# PCIe.net
KiCad netlist of a schematic drawn in Altium Designer
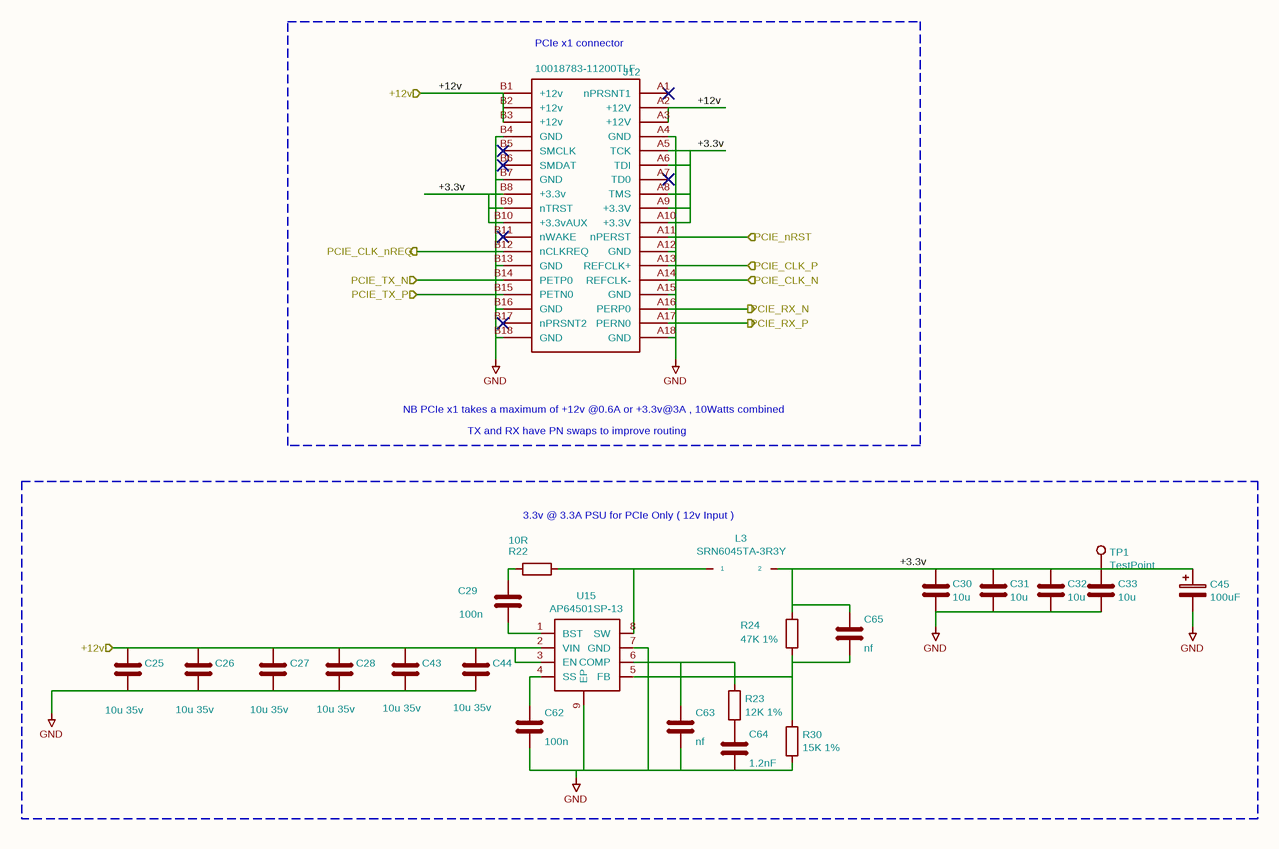
[diagram p0: PCIe.SchDoc]

(export (version "E")
  (design (tool "Eeschema 10.0.6"))
  (components
    (comp (ref "C25") (value "10u 35v") (libsource (lib "Device") (part "C")))
    (comp (ref "C26") (value "10u 35v") (libsource (lib "Device") (part "C")))
    (comp (ref "C27") (value "10u 35v") (libsource (lib "Device") (part "C")))
    (comp (ref "C28") (value "10u 35v") (libsource (lib "Device") (part "C")))
    (comp (ref "C29") (value "100n") (libsource (lib "Device") (part "C")))
    (comp (ref "C30") (value "10u") (libsource (lib "Device") (part "C")))
    (comp (ref "C31") (value "10u") (libsource (lib "Device") (part "C")))
    (comp (ref "C32") (value "10u") (libsource (lib "Device") (part "C")))
    (comp (ref "C33") (value "10u") (libsource (lib "Device") (part "C")))
    (comp (ref "C43") (value "10u 35v") (libsource (lib "Device") (part "C")))
    (comp (ref "C44") (value "10u 35v") (libsource (lib "Device") (part "C")))
    (comp (ref "C45") (value "100uF") (libsource (lib "Device") (part "CP")))
    (comp (ref "C62") (value "100n") (libsource (lib "Device") (part "C")))
    (comp (ref "C63") (value "nf") (libsource (lib "Device") (part "C")))
    (comp (ref "C64") (value "1.2nF") (libsource (lib "Device") (part "C")))
    (comp (ref "C65") (value "nf") (libsource (lib "Device") (part "C")))
    (comp (ref "J12") (value "10018783-11200TLF") (libsource (lib "CM4IO") (part "PCIe-x1")))
    (comp (ref "L3") (value "SRN6045TA-3R3Y") (libsource (lib "pspice") (part "INDUCTOR")))
    (comp (ref "R22") (value "10R") (libsource (lib "") (part "R_1")))
    (comp (ref "R23") (value "12K 1%") (libsource (lib "Device") (part "R")))
    (comp (ref "R24") (value "47K 1%") (libsource (lib "Device") (part "R")))
    (comp (ref "R30") (value "15K 1%") (libsource (lib "Device") (part "R")))
    (comp (ref "TP1") (value "TestPoint") (libsource (lib "Connector") (part "TestPoint")))
    (comp (ref "U15") (value "AP64501SP-13") (libsource (lib "CM4IO") (part "AP64351")))
  )
  (nets
    (net (code "1") (name "/+3.3v") (class "Default")
      (node (ref "C30") (pin "1") (pinfunction "1_1") (pintype "passive"))
      (node (ref "C31") (pin "1") (pinfunction "1_1") (pintype "passive"))
      (node (ref "C32") (pin "1") (pinfunction "1_1") (pintype "passive"))
      (node (ref "C33") (pin "1") (pinfunction "1_1") (pintype "passive"))
      (node (ref "C45") (pin "1") (pinfunction "1_1") (pintype "passive"))
      (node (ref "C65") (pin "1") (pinfunction "1_1") (pintype "passive"))
      (node (ref "J12") (pin "A10") (pinfunction "+3.3V_A10") (pintype "passive"))
      (node (ref "J12") (pin "A5") (pinfunction "TCK_A5") (pintype "passive"))
      (node (ref "J12") (pin "A6") (pinfunction "TDI_A6") (pintype "passive"))
      (node (ref "J12") (pin "A8") (pinfunction "TMS_A8") (pintype "passive"))
      (node (ref "J12") (pin "A9") (pinfunction "+3.3V_A9") (pintype "passive"))
      (node (ref "J12") (pin "B10") (pinfunction "+3.3vAUX_B10") (pintype "passive"))
      (node (ref "J12") (pin "B8") (pinfunction "+3.3v_B8") (pintype "passive"))
      (node (ref "J12") (pin "B9") (pinfunction "nTRST_B9") (pintype "passive"))
      (node (ref "L3") (pin "2") (pinfunction "2_2") (pintype "passive"))
      (node (ref "R24") (pin "1") (pinfunction "1_1") (pintype "passive"))
      (node (ref "TP1") (pin "1") (pinfunction "1_1") (pintype "passive"))
    )
    (net (code "2") (name "/+12v") (class "Default")
      (node (ref "C25") (pin "1") (pinfunction "1_1") (pintype "passive"))
      (node (ref "C26") (pin "1") (pinfunction "1_1") (pintype "passive"))
      (node (ref "C27") (pin "1") (pinfunction "1_1") (pintype "passive"))
      (node (ref "C28") (pin "1") (pinfunction "1_1") (pintype "passive"))
      (node (ref "C43") (pin "1") (pinfunction "1_1") (pintype "passive"))
      (node (ref "C44") (pin "1") (pinfunction "1_1") (pintype "passive"))
      (node (ref "J12") (pin "A2") (pinfunction "+12V_A2") (pintype "passive"))
      (node (ref "J12") (pin "A3") (pinfunction "+12V_A3") (pintype "passive"))
      (node (ref "J12") (pin "B1") (pinfunction "+12v_B1") (pintype "passive"))
      (node (ref "J12") (pin "B2") (pinfunction "+12v_B2") (pintype "passive"))
      (node (ref "J12") (pin "B3") (pinfunction "+12v_B3") (pintype "passive"))
      (node (ref "U15") (pin "2") (pinfunction "VIN_2") (pintype "passive"))
      (node (ref "U15") (pin "3") (pinfunction "EN_3") (pintype "passive"))
    )
    (net (code "3") (name "/PCIE_CLK_N") (class "Default")
      (node (ref "J12") (pin "A14") (pinfunction "REFCLK-_A14") (pintype "passive"))
    )
    (net (code "4") (name "/PCIE_CLK_P") (class "Default")
      (node (ref "J12") (pin "A13") (pinfunction "REFCLK+_A13") (pintype "passive"))
    )
    (net (code "5") (name "/PCIE_CLK_nREQ") (class "Default")
      (node (ref "J12") (pin "B12") (pinfunction "nCLKREQ_B12") (pintype "passive"))
    )
    (net (code "6") (name "/PCIE_RX_N") (class "Default")
      (node (ref "J12") (pin "A16") (pinfunction "PERP0_A16") (pintype "passive"))
    )
    (net (code "7") (name "/PCIE_RX_P") (class "Default")
      (node (ref "J12") (pin "A17") (pinfunction "PERN0_A17") (pintype "passive"))
    )
    (net (code "8") (name "/PCIE_TX_N") (class "Default")
      (node (ref "J12") (pin "B14") (pinfunction "PETP0_B14") (pintype "passive"))
    )
    (net (code "9") (name "/PCIE_TX_P") (class "Default")
      (node (ref "J12") (pin "B15") (pinfunction "PETN0_B15") (pintype "passive"))
    )
    (net (code "10") (name "/PCIE_nRST") (class "Default")
      (node (ref "J12") (pin "A11") (pinfunction "nPERST_A11") (pintype "passive"))
    )
    (net (code "11") (name "GND") (class "Default")
      (node (ref "C25") (pin "2") (pinfunction "2_2") (pintype "passive"))
      (node (ref "C26") (pin "2") (pinfunction "2_2") (pintype "passive"))
      (node (ref "C27") (pin "2") (pinfunction "2_2") (pintype "passive"))
      (node (ref "C28") (pin "2") (pinfunction "2_2") (pintype "passive"))
      (node (ref "C30") (pin "2") (pinfunction "2_2") (pintype "passive"))
      (node (ref "C31") (pin "2") (pinfunction "2_2") (pintype "passive"))
      (node (ref "C32") (pin "2") (pinfunction "2_2") (pintype "passive"))
      (node (ref "C33") (pin "2") (pinfunction "2_2") (pintype "passive"))
      (node (ref "C43") (pin "2") (pinfunction "2_2") (pintype "passive"))
      (node (ref "C44") (pin "2") (pinfunction "2_2") (pintype "passive"))
      (node (ref "C45") (pin "2") (pinfunction "2_2") (pintype "passive"))
      (node (ref "C62") (pin "2") (pinfunction "2_2") (pintype "passive"))
      (node (ref "C63") (pin "2") (pinfunction "2_2") (pintype "passive"))
      (node (ref "C64") (pin "2") (pinfunction "2_2") (pintype "passive"))
      (node (ref "J12") (pin "A12") (pinfunction "GND_A12") (pintype "passive"))
      (node (ref "J12") (pin "A15") (pinfunction "GND_A15") (pintype "passive"))
      (node (ref "J12") (pin "A18") (pinfunction "GND_A18") (pintype "passive"))
      (node (ref "J12") (pin "A4") (pinfunction "GND_A4") (pintype "passive"))
      (node (ref "J12") (pin "B13") (pinfunction "GND_B13") (pintype "passive"))
      (node (ref "J12") (pin "B16") (pinfunction "GND_B16") (pintype "passive"))
      (node (ref "J12") (pin "B18") (pinfunction "GND_B18") (pintype "passive"))
      (node (ref "J12") (pin "B4") (pinfunction "GND_B4") (pintype "passive"))
      (node (ref "J12") (pin "B7") (pinfunction "GND_B7") (pintype "passive"))
      (node (ref "R30") (pin "2") (pinfunction "2_2") (pintype "passive"))
      (node (ref "U15") (pin "7") (pinfunction "GND_7") (pintype "passive"))
      (node (ref "U15") (pin "9") (pinfunction "EP_9") (pintype "passive"))
    )
    (net (code "12") (name "Net-(C29-Pad1)") (class "Default")
      (node (ref "C29") (pin "1") (pinfunction "1_1") (pintype "passive"))
      (node (ref "R22") (pin "2") (pinfunction "2_2") (pintype "passive"))
    )
    (net (code "13") (name "Net-(C64-Pad1)") (class "Default")
      (node (ref "C64") (pin "1") (pinfunction "1_1") (pintype "passive"))
      (node (ref "R23") (pin "2") (pinfunction "2_2") (pintype "passive"))
    )
    (net (code "14") (name "Net-(U15-BST)") (class "Default")
      (node (ref "C29") (pin "2") (pinfunction "2_2") (pintype "passive"))
      (node (ref "U15") (pin "1") (pinfunction "BST_1") (pintype "passive"))
    )
    (net (code "15") (name "Net-(U15-COMP)") (class "Default")
      (node (ref "C63") (pin "1") (pinfunction "1_1") (pintype "passive"))
      (node (ref "R23") (pin "1") (pinfunction "1_1") (pintype "passive"))
      (node (ref "U15") (pin "6") (pinfunction "COMP_6") (pintype "passive"))
    )
    (net (code "16") (name "Net-(U15-FB)") (class "Default")
      (node (ref "C65") (pin "2") (pinfunction "2_2") (pintype "passive"))
      (node (ref "R24") (pin "2") (pinfunction "2_2") (pintype "passive"))
      (node (ref "R30") (pin "1") (pinfunction "1_1") (pintype "passive"))
      (node (ref "U15") (pin "5") (pinfunction "FB_5") (pintype "passive"))
    )
    (net (code "17") (name "Net-(U15-SS)") (class "Default")
      (node (ref "C62") (pin "1") (pinfunction "1_1") (pintype "passive"))
      (node (ref "U15") (pin "4") (pinfunction "SS_4") (pintype "passive"))
    )
    (net (code "18") (name "Net-(U15-SW)") (class "Default")
      (node (ref "L3") (pin "1") (pinfunction "1_1") (pintype "passive"))
      (node (ref "R22") (pin "1") (pinfunction "1_1") (pintype "passive"))
      (node (ref "U15") (pin "8") (pinfunction "SW_8") (pintype "passive"))
    )
    (net (code "19") (name "unconnected-(J12-SMCLK-PadB5)") (class "Default")
      (node (ref "J12") (pin "B5") (pinfunction "SMCLK_B5") (pintype "passive+no_connect"))
    )
    (net (code "20") (name "unconnected-(J12-SMDAT-PadB6)") (class "Default")
      (node (ref "J12") (pin "B6") (pinfunction "SMDAT_B6") (pintype "passive+no_connect"))
    )
    (net (code "21") (name "unconnected-(J12-TD0-PadA7)") (class "Default")
      (node (ref "J12") (pin "A7") (pinfunction "TD0_A7") (pintype "passive+no_connect"))
    )
    (net (code "22") (name "unconnected-(J12-nPRSNT1-PadA1)") (class "Default")
      (node (ref "J12") (pin "A1") (pinfunction "nPRSNT1_A1") (pintype "passive+no_connect"))
    )
    (net (code "23") (name "unconnected-(J12-nPRSNT2-PadB17)") (class "Default")
      (node (ref "J12") (pin "B17") (pinfunction "nPRSNT2_B17") (pintype "passive+no_connect"))
    )
    (net (code "24") (name "unconnected-(J12-nWAKE-PadB11)") (class "Default")
      (node (ref "J12") (pin "B11") (pinfunction "nWAKE_B11") (pintype "passive+no_connect"))
    )
  )
)
